# newKalathi.net
KiCad netlist of a schematic drawn in EAGLE
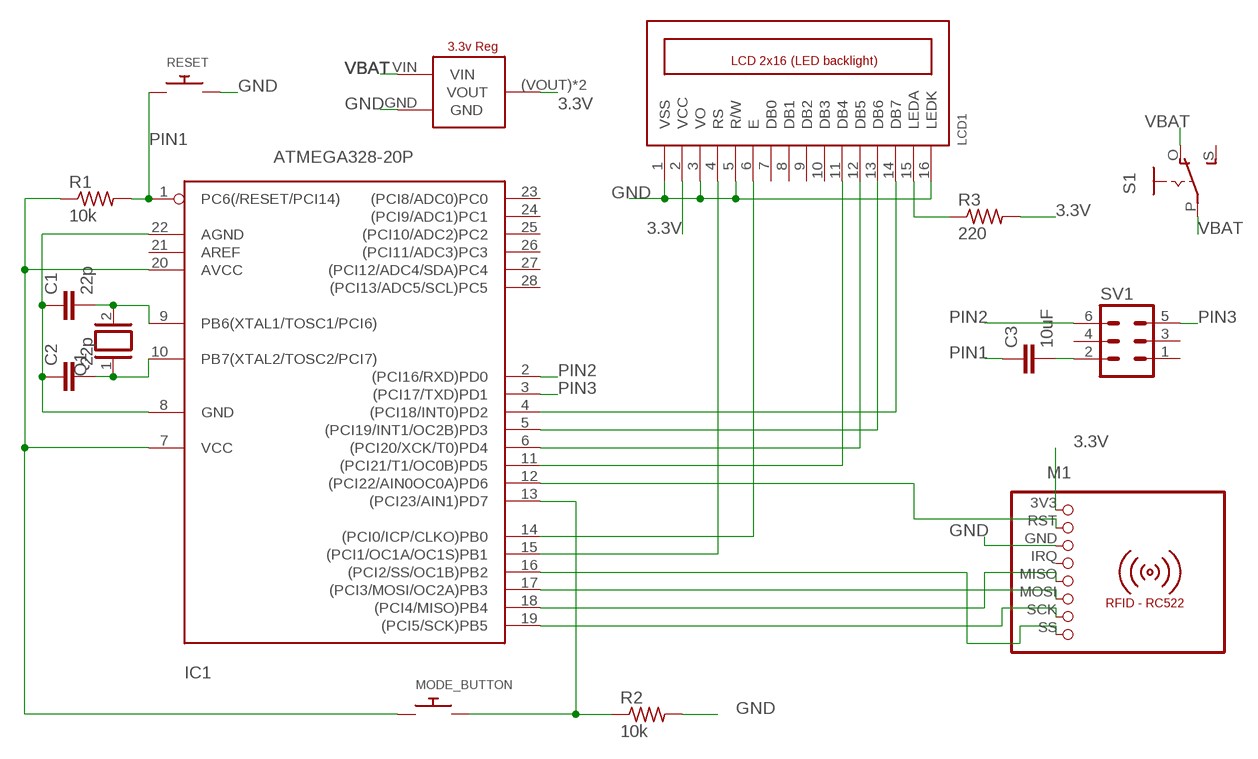
[diagram p0: schematic, sheet 1]

(export (version "E")
  (design (tool "Eeschema 10.0.6"))
  (components
    (comp (ref "C1")
      (value "22p")
      (footprint "eagle-import:C2.5-3")
      (libsource (lib "eagle-import") (part "C2,5-3"))
    )
    (comp (ref "C2")
      (value "22p")
      (footprint "eagle-import:C2.5-3")
      (libsource (lib "eagle-import") (part "C2,5-3"))
    )
    (comp (ref "C3")
      (value "10uF")
      (footprint "eagle-import:C5B3")
      (libsource (lib "eagle-import") (part "C5/3"))
    )
    (comp (ref "IC1")
      (value "ATMEGA328-20P")
      (footprint "eagle-import:DIL28-3")
      (libsource (lib "eagle-import") (part "ATMEGA328P-20"))
    )
    (comp (ref "LCD1")
      (value "LCD_2X16_SIL")
      (footprint "eagle-import:HY-1602F")
      (libsource (lib "eagle-import") (part "LCD_2X16_SIL"))
    )
    (comp (ref "M1")
      (value "RFID-RC522")
      (footprint "eagle-import:RFID-RC522")
      (libsource (lib "eagle-import") (part "RFID-RC522"))
    )
    (comp (ref "MODE_BUTTON")
      (value "SWITCH_PUSHBUTTONEVQ-PE")
      (footprint "eagle-import:TACT_PANA-EVQ")
      (libsource (lib "eagle-import") (part "SWITCH_PUSHBUTTONEVQ-PE"))
    )
    (comp (ref "Q1")
      (value "XTAL")
      (footprint "eagle-import:Q")
      (libsource (lib "eagle-import") (part "XTAL"))
    )
    (comp (ref "R1")
      (value "10k")
      (footprint "eagle-import:0204_7")
      (libsource (lib "eagle-import") (part "R-US_0204/7"))
    )
    (comp (ref "R2")
      (value "10k")
      (footprint "eagle-import:0204_7")
      (libsource (lib "eagle-import") (part "R-US_0204/7"))
    )
    (comp (ref "R3")
      (value "220")
      (footprint "eagle-import:0204_7")
      (libsource (lib "eagle-import") (part "R-US_0204/7"))
    )
    (comp (ref "RESET")
      (value "SWITCH_PUSHBUTTONEVQ-PE")
      (footprint "eagle-import:TACT_PANA-EVQ")
      (libsource (lib "eagle-import") (part "SWITCH_PUSHBUTTONEVQ-PE"))
    )
    (comp (ref "S1")
      (value "EG1218S")
      (footprint "eagle-import:EG1218")
      (libsource (lib "eagle-import") (part "EG1218S"))
    )
    (comp (ref "SV1")
      (value "MA03-2")
      (footprint "eagle-import:MA03-2")
      (libsource (lib "eagle-import") (part "MA03-2"))
    )
    (comp (ref "U$1")
      (value "LD1117")
      (footprint "eagle-import:LD1117SOT-223")
      (libsource (lib "eagle-import") (part "LD1117"))
    )
  )
  (nets
    (net (code "1") (name "/3.3V") (class "Default")
      (node (ref "IC1") (pin "20") (pinfunction "AVCC_20") (pintype "bidirectional"))
      (node (ref "IC1") (pin "7") (pinfunction "VCC_7") (pintype "bidirectional"))
      (node (ref "LCD1") (pin "2") (pinfunction "VCC_2") (pintype "power_in"))
      (node (ref "M1") (pin "3V3") (pinfunction "1_3V3") (pintype "passive"))
      (node (ref "MODE_BUTTON") (pin "P$1") (pinfunction "P$1_P$1") (pintype "passive"))
      (node (ref "R1") (pin "1") (pinfunction "1_1") (pintype "passive"))
      (node (ref "R3") (pin "2") (pinfunction "2_2") (pintype "passive"))
      (node (ref "U$1") (pin "(VOUT)") (pinfunction "VOUT_(VOUT)") (pintype "bidirectional"))
      (node (ref "U$1") (pin "VOUT") (pinfunction "VOUT_VOUT") (pintype "bidirectional"))
    )
    (net (code "2") (name "/GND") (class "Default")
      (node (ref "C1") (pin "1") (pinfunction "1_1") (pintype "passive"))
      (node (ref "C2") (pin "1") (pinfunction "1_1") (pintype "passive"))
      (node (ref "IC1") (pin "22") (pinfunction "AGND_22") (pintype "bidirectional"))
      (node (ref "IC1") (pin "8") (pinfunction "GND_8") (pintype "bidirectional"))
      (node (ref "LCD1") (pin "1") (pinfunction "VSS_1") (pintype "power_in"))
      (node (ref "LCD1") (pin "16") (pinfunction "LEDK_16") (pintype "passive"))
      (node (ref "LCD1") (pin "3") (pinfunction "VO_3") (pintype "input"))
      (node (ref "LCD1") (pin "5") (pinfunction "R/W_5") (pintype "input"))
      (node (ref "M1") (pin "GND") (pinfunction "3_GND") (pintype "passive"))
      (node (ref "R2") (pin "2") (pinfunction "2_2") (pintype "passive"))
      (node (ref "RESET") (pin "P$2") (pinfunction "P$2_P$2") (pintype "passive"))
      (node (ref "U$1") (pin "GND") (pinfunction "GND_GND") (pintype "bidirectional"))
    )
    (net (code "3") (name "/PIN1") (class "Default")
      (node (ref "C3") (pin "1") (pinfunction "1_1") (pintype "passive"))
      (node (ref "IC1") (pin "1") (pinfunction "PC6(/RESET/PCI14)_1") (pintype "bidirectional"))
      (node (ref "R1") (pin "2") (pinfunction "2_2") (pintype "passive"))
      (node (ref "RESET") (pin "P$1") (pinfunction "P$1_P$1") (pintype "passive"))
    )
    (net (code "4") (name "/PIN2") (class "Default")
      (node (ref "IC1") (pin "2") (pinfunction "(PCI16/RXD)PD0_2") (pintype "bidirectional"))
      (node (ref "SV1") (pin "6") (pinfunction "6_6") (pintype "passive"))
    )
    (net (code "5") (name "/PIN3") (class "Default")
      (node (ref "IC1") (pin "3") (pinfunction "(PCI17/TXD)PD1_3") (pintype "bidirectional"))
      (node (ref "SV1") (pin "5") (pinfunction "5_5") (pintype "passive"))
    )
    (net (code "6") (name "/VBAT") (class "Default")
      (node (ref "S1") (pin "O") (pinfunction "O_O") (pintype "passive"))
      (node (ref "S1") (pin "P") (pinfunction "P_P") (pintype "passive"))
      (node (ref "U$1") (pin "VIN") (pinfunction "VIN_VIN") (pintype "bidirectional"))
    )
    (net (code "7") (name "Net-(C3-Pad2)") (class "Default")
      (node (ref "C3") (pin "2") (pinfunction "2_2") (pintype "passive"))
      (node (ref "SV1") (pin "2") (pinfunction "2_2") (pintype "passive"))
    )
    (net (code "8") (name "Net-(IC1-(PCI0{slash}ICP{slash}CLKO)PB0)") (class "Default")
      (node (ref "IC1") (pin "14") (pinfunction "(PCI0/ICP/CLKO)PB0_14") (pintype "bidirectional"))
      (node (ref "LCD1") (pin "6") (pinfunction "E_6") (pintype "input"))
    )
    (net (code "9") (name "Net-(IC1-(PCI1{slash}OC1A{slash}OC1S)PB1)") (class "Default")
      (node (ref "IC1") (pin "15") (pinfunction "(PCI1/OC1A/OC1S)PB1_15") (pintype "bidirectional"))
      (node (ref "LCD1") (pin "4") (pinfunction "RS_4") (pintype "input"))
    )
    (net (code "10") (name "Net-(IC1-(PCI2{slash}SS{slash}OC1B)PB2)") (class "Default")
      (node (ref "IC1") (pin "16") (pinfunction "(PCI2/SS/OC1B)PB2_16") (pintype "bidirectional"))
      (node (ref "M1") (pin "SS") (pinfunction "8_SS") (pintype "passive"))
    )
    (net (code "11") (name "Net-(IC1-(PCI3{slash}MOSI{slash}OC2A)PB3)") (class "Default")
      (node (ref "IC1") (pin "17") (pinfunction "(PCI3/MOSI/OC2A)PB3_17") (pintype "bidirectional"))
      (node (ref "M1") (pin "MOSI") (pinfunction "6_MOSI") (pintype "passive"))
    )
    (net (code "12") (name "Net-(IC1-(PCI4{slash}MISO)PB4)") (class "Default")
      (node (ref "IC1") (pin "18") (pinfunction "(PCI4/MISO)PB4_18") (pintype "bidirectional"))
      (node (ref "M1") (pin "MISO") (pinfunction "5_MISO") (pintype "passive"))
    )
    (net (code "13") (name "Net-(IC1-(PCI5{slash}SCK)PB5)") (class "Default")
      (node (ref "IC1") (pin "19") (pinfunction "(PCI5/SCK)PB5_19") (pintype "bidirectional"))
      (node (ref "M1") (pin "SCK") (pinfunction "7_SCK") (pintype "passive"))
    )
    (net (code "14") (name "Net-(IC1-(PCI18{slash}INT0)PD2)") (class "Default")
      (node (ref "IC1") (pin "4") (pinfunction "(PCI18/INT0)PD2_4") (pintype "bidirectional"))
      (node (ref "LCD1") (pin "14") (pinfunction "DB7_14") (pintype "bidirectional"))
    )
    (net (code "15") (name "Net-(IC1-(PCI19{slash}INT1{slash}OC2B)PD3)") (class "Default")
      (node (ref "IC1") (pin "5") (pinfunction "(PCI19/INT1/OC2B)PD3_5") (pintype "bidirectional"))
      (node (ref "LCD1") (pin "13") (pinfunction "DB6_13") (pintype "bidirectional"))
    )
    (net (code "16") (name "Net-(IC1-(PCI20{slash}XCK{slash}T0)PD4)") (class "Default")
      (node (ref "IC1") (pin "6") (pinfunction "(PCI20/XCK/T0)PD4_6") (pintype "bidirectional"))
      (node (ref "LCD1") (pin "12") (pinfunction "DB5_12") (pintype "bidirectional"))
    )
    (net (code "17") (name "Net-(IC1-(PCI21{slash}T1{slash}OC0B)PD5)") (class "Default")
      (node (ref "IC1") (pin "11") (pinfunction "(PCI21/T1/OC0B)PD5_11") (pintype "bidirectional"))
      (node (ref "LCD1") (pin "11") (pinfunction "DB4_11") (pintype "bidirectional"))
    )
    (net (code "18") (name "Net-(IC1-(PCI22{slash}AIN0OC0A)PD6)") (class "Default")
      (node (ref "IC1") (pin "12") (pinfunction "(PCI22/AIN0OC0A)PD6_12") (pintype "bidirectional"))
      (node (ref "M1") (pin "RST") (pinfunction "2_RST") (pintype "passive"))
    )
    (net (code "19") (name "Net-(IC1-(PCI23{slash}AIN1)PD7)") (class "Default")
      (node (ref "IC1") (pin "13") (pinfunction "(PCI23/AIN1)PD7_13") (pintype "bidirectional"))
      (node (ref "MODE_BUTTON") (pin "P$2") (pinfunction "P$2_P$2") (pintype "passive"))
      (node (ref "R2") (pin "1") (pinfunction "1_1") (pintype "passive"))
    )
    (net (code "20") (name "Net-(IC1-PB6(XTAL1{slash}TOSC1{slash}PCI6))") (class "Default")
      (node (ref "C1") (pin "2") (pinfunction "2_2") (pintype "passive"))
      (node (ref "IC1") (pin "9") (pinfunction "PB6(XTAL1/TOSC1/PCI6)_9") (pintype "bidirectional"))
      (node (ref "Q1") (pin "2") (pinfunction "2_2") (pintype "passive"))
    )
    (net (code "21") (name "Net-(IC1-PB7(XTAL2{slash}TOSC2{slash}PCI7))") (class "Default")
      (node (ref "C2") (pin "2") (pinfunction "2_2") (pintype "passive"))
      (node (ref "IC1") (pin "10") (pinfunction "PB7(XTAL2/TOSC2/PCI7)_10") (pintype "bidirectional"))
      (node (ref "Q1") (pin "1") (pinfunction "1_1") (pintype "passive"))
    )
    (net (code "22") (name "Net-(LCD1-LEDA)") (class "Default")
      (node (ref "LCD1") (pin "15") (pinfunction "LEDA_15") (pintype "passive"))
      (node (ref "R3") (pin "1") (pinfunction "1_1") (pintype "passive"))
    )
    (net (code "23") (name "unconnected-(IC1-(PCI8{slash}ADC0)PC0-Pad23)") (class "Default")
      (node (ref "IC1") (pin "23") (pinfunction "(PCI8/ADC0)PC0_23") (pintype "bidirectional"))
    )
    (net (code "24") (name "unconnected-(IC1-(PCI9{slash}ADC1)PC1-Pad24)") (class "Default")
      (node (ref "IC1") (pin "24") (pinfunction "(PCI9/ADC1)PC1_24") (pintype "bidirectional"))
    )
    (net (code "25") (name "unconnected-(IC1-(PCI10{slash}ADC2)PC2-Pad25)") (class "Default")
      (node (ref "IC1") (pin "25") (pinfunction "(PCI10/ADC2)PC2_25") (pintype "bidirectional"))
    )
    (net (code "26") (name "unconnected-(IC1-(PCI11{slash}ADC3)PC3-Pad26)") (class "Default")
      (node (ref "IC1") (pin "26") (pinfunction "(PCI11/ADC3)PC3_26") (pintype "bidirectional"))
    )
    (net (code "27") (name "unconnected-(IC1-(PCI12{slash}ADC4{slash}SDA)PC4-Pad27)") (class "Default")
      (node (ref "IC1") (pin "27") (pinfunction "(PCI12/ADC4/SDA)PC4_27") (pintype "bidirectional"))
    )
    (net (code "28") (name "unconnected-(IC1-(PCI13{slash}ADC5{slash}SCL)PC5-Pad28)") (class "Default")
      (node (ref "IC1") (pin "28") (pinfunction "(PCI13/ADC5/SCL)PC5_28") (pintype "bidirectional"))
    )
    (net (code "29") (name "unconnected-(IC1-AREF-Pad21)") (class "Default")
      (node (ref "IC1") (pin "21") (pinfunction "AREF_21") (pintype "bidirectional"))
    )
    (net (code "30") (name "unconnected-(LCD1-DB0-Pad7)") (class "Default")
      (node (ref "LCD1") (pin "7") (pinfunction "DB0_7") (pintype "bidirectional"))
    )
    (net (code "31") (name "unconnected-(LCD1-DB1-Pad8)") (class "Default")
      (node (ref "LCD1") (pin "8") (pinfunction "DB1_8") (pintype "bidirectional"))
    )
    (net (code "32") (name "unconnected-(LCD1-DB2-Pad9)") (class "Default")
      (node (ref "LCD1") (pin "9") (pinfunction "DB2_9") (pintype "bidirectional"))
    )
    (net (code "33") (name "unconnected-(LCD1-DB3-Pad10)") (class "Default")
      (node (ref "LCD1") (pin "10") (pinfunction "DB3_10") (pintype "bidirectional"))
    )
    (net (code "34") (name "unconnected-(M1-4-PadIRQ)") (class "Default")
      (node (ref "M1") (pin "IRQ") (pinfunction "4_IRQ") (pintype "passive"))
    )
    (net (code "35") (name "unconnected-(S1-PadS)") (class "Default")
      (node (ref "S1") (pin "S") (pinfunction "S_S") (pintype "passive"))
    )
    (net (code "36") (name "unconnected-(SV1-Pad1)") (class "Default")
      (node (ref "SV1") (pin "1") (pinfunction "1_1") (pintype "passive"))
    )
    (net (code "37") (name "unconnected-(SV1-Pad3)") (class "Default")
      (node (ref "SV1") (pin "3") (pinfunction "3_3") (pintype "passive"))
    )
    (net (code "38") (name "unconnected-(SV1-Pad4)") (class "Default")
      (node (ref "SV1") (pin "4") (pinfunction "4_4") (pintype "passive"))
    )
  )
)
